# miniProIR.net
KiCad netlist of a schematic drawn in EAGLE
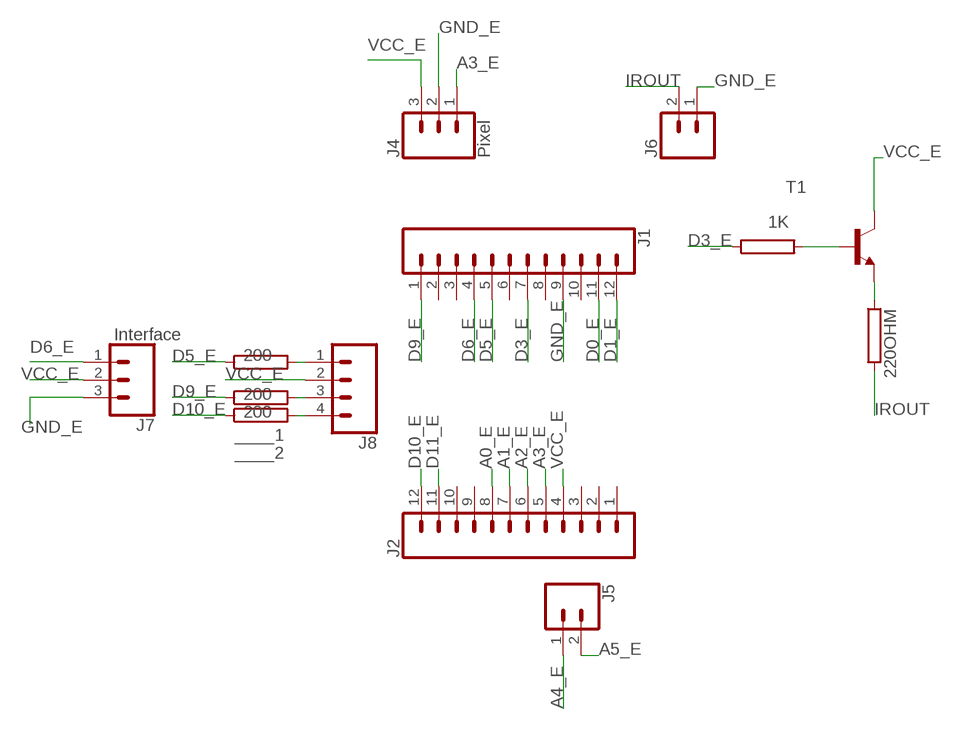
[diagram p0: schematic, sheet 1]

(export (version "E")
  (design (tool "Eeschema 10.0.6"))
  (components
    (comp (ref "1K")
      (value "RCA0001")
      (footprint "eagle-import:CA0001")
      (libsource (lib "eagle-import") (part "RCA0001"))
    )
    (comp (ref "200")
      (value "RCA0001")
      (footprint "eagle-import:CA0001")
      (libsource (lib "eagle-import") (part "RCA0001"))
    )
    (comp (ref "220OHM")
      (value "RCA0001")
      (footprint "eagle-import:CA0001")
      (libsource (lib "eagle-import") (part "RCA0001"))
    )
    (comp (ref "J1")
      (value "CONN_12")
      (footprint "eagle-import:1X12")
      (libsource (lib "eagle-import") (part "CONN_12"))
    )
    (comp (ref "J2")
      (value "CONN_12")
      (footprint "eagle-import:1X12")
      (libsource (lib "eagle-import") (part "CONN_12"))
    )
    (comp (ref "J4")
      (value "Pixel")
      (footprint "eagle-import:1X03")
      (libsource (lib "eagle-import") (part "CONN_03"))
    )
    (comp (ref "J5")
      (value "CONN_02")
      (footprint "eagle-import:1X02")
      (libsource (lib "eagle-import") (part "CONN_02"))
    )
    (comp (ref "J6")
      (value "CONN_02")
      (footprint "eagle-import:1X02")
      (libsource (lib "eagle-import") (part "CONN_02"))
    )
    (comp (ref "J7")
      (value "Interface")
      (footprint "eagle-import:1X03")
      (libsource (lib "eagle-import") (part "CONN_03"))
    )
    (comp (ref "J8")
      (value "CONN_04")
      (footprint "eagle-import:1X04")
      (libsource (lib "eagle-import") (part "CONN_04"))
    )
    (comp (ref "T1")
      (value "29-NPN-TO92-EBC")
      (footprint "eagle-import:TO92-EBC")
      (libsource (lib "eagle-import") (part "-NPN-TO92-EBC29"))
    )
    (comp (ref "____1")
      (value "200")
      (footprint "eagle-import:CA0001")
      (libsource (lib "eagle-import") (part "RCA0001"))
    )
    (comp (ref "____2")
      (value "200")
      (footprint "eagle-import:CA0001")
      (libsource (lib "eagle-import") (part "RCA0001"))
    )
  )
  (nets
    (net (code "1") (name "/A0_E") (class "Default")
      (node (ref "J2") (pin "8") (pinfunction "8_8") (pintype "passive"))
    )
    (net (code "2") (name "/A1_E") (class "Default")
      (node (ref "J2") (pin "7") (pinfunction "7_7") (pintype "passive"))
    )
    (net (code "3") (name "/A2_E") (class "Default")
      (node (ref "J2") (pin "6") (pinfunction "6_6") (pintype "passive"))
    )
    (net (code "4") (name "/A3_E") (class "Default")
      (node (ref "J2") (pin "5") (pinfunction "5_5") (pintype "passive"))
      (node (ref "J4") (pin "1") (pinfunction "1_1") (pintype "passive"))
    )
    (net (code "5") (name "/A4_E") (class "Default")
      (node (ref "J5") (pin "1") (pinfunction "1_1") (pintype "passive"))
    )
    (net (code "6") (name "/A5_E") (class "Default")
      (node (ref "J5") (pin "2") (pinfunction "2_2") (pintype "passive"))
    )
    (net (code "7") (name "/D0_E") (class "Default")
      (node (ref "J1") (pin "11") (pinfunction "11_11") (pintype "passive"))
    )
    (net (code "8") (name "/D1_E") (class "Default")
      (node (ref "J1") (pin "12") (pinfunction "12_12") (pintype "passive"))
    )
    (net (code "9") (name "/D3_E") (class "Default")
      (node (ref "1K") (pin "1") (pinfunction "1_1") (pintype "passive"))
      (node (ref "J1") (pin "7") (pinfunction "7_7") (pintype "passive"))
    )
    (net (code "10") (name "/D5_E") (class "Default")
      (node (ref "200") (pin "1") (pinfunction "1_1") (pintype "passive"))
      (node (ref "J1") (pin "5") (pinfunction "5_5") (pintype "passive"))
    )
    (net (code "11") (name "/D6_E") (class "Default")
      (node (ref "J1") (pin "4") (pinfunction "4_4") (pintype "passive"))
      (node (ref "J7") (pin "1") (pinfunction "1_1") (pintype "passive"))
    )
    (net (code "12") (name "/D9_E") (class "Default")
      (node (ref "J1") (pin "1") (pinfunction "1_1") (pintype "passive"))
      (node (ref "____1") (pin "1") (pinfunction "1_1") (pintype "passive"))
    )
    (net (code "13") (name "/D10_E") (class "Default")
      (node (ref "J2") (pin "12") (pinfunction "12_12") (pintype "passive"))
      (node (ref "____2") (pin "1") (pinfunction "1_1") (pintype "passive"))
    )
    (net (code "14") (name "/D11_E") (class "Default")
      (node (ref "J2") (pin "11") (pinfunction "11_11") (pintype "passive"))
    )
    (net (code "15") (name "/GND_E") (class "Default")
      (node (ref "J1") (pin "9") (pinfunction "9_9") (pintype "passive"))
      (node (ref "J4") (pin "2") (pinfunction "2_2") (pintype "passive"))
      (node (ref "J6") (pin "1") (pinfunction "1_1") (pintype "passive"))
      (node (ref "J7") (pin "3") (pinfunction "3_3") (pintype "passive"))
    )
    (net (code "16") (name "/IROUT") (class "Default")
      (node (ref "220OHM") (pin "2") (pinfunction "2_2") (pintype "passive"))
      (node (ref "J6") (pin "2") (pinfunction "2_2") (pintype "passive"))
    )
    (net (code "17") (name "/VCC_E") (class "Default")
      (node (ref "J2") (pin "4") (pinfunction "4_4") (pintype "passive"))
      (node (ref "J4") (pin "3") (pinfunction "3_3") (pintype "passive"))
      (node (ref "J7") (pin "2") (pinfunction "2_2") (pintype "passive"))
      (node (ref "J8") (pin "2") (pinfunction "2_2") (pintype "passive"))
      (node (ref "T1") (pin "C") (pinfunction "C_C") (pintype "passive"))
    )
    (net (code "18") (name "Net-(1K-Pad2)") (class "Default")
      (node (ref "1K") (pin "2") (pinfunction "2_2") (pintype "passive"))
      (node (ref "T1") (pin "B") (pinfunction "B_B") (pintype "passive"))
    )
    (net (code "19") (name "Net-(200-Pad2)") (class "Default")
      (node (ref "200") (pin "2") (pinfunction "2_2") (pintype "passive"))
      (node (ref "J8") (pin "1") (pinfunction "1_1") (pintype "passive"))
    )
    (net (code "20") (name "Net-(220OHM-Pad1)") (class "Default")
      (node (ref "220OHM") (pin "1") (pinfunction "1_1") (pintype "passive"))
      (node (ref "T1") (pin "E") (pinfunction "E_E") (pintype "passive"))
    )
    (net (code "21") (name "Net-(J8-Pad3)") (class "Default")
      (node (ref "J8") (pin "3") (pinfunction "3_3") (pintype "passive"))
      (node (ref "____1") (pin "2") (pinfunction "2_2") (pintype "passive"))
    )
    (net (code "22") (name "Net-(J8-Pad4)") (class "Default")
      (node (ref "J8") (pin "4") (pinfunction "4_4") (pintype "passive"))
      (node (ref "____2") (pin "2") (pinfunction "2_2") (pintype "passive"))
    )
    (net (code "23") (name "unconnected-(J1-Pad2)") (class "Default")
      (node (ref "J1") (pin "2") (pinfunction "2_2") (pintype "passive"))
    )
    (net (code "24") (name "unconnected-(J1-Pad3)") (class "Default")
      (node (ref "J1") (pin "3") (pinfunction "3_3") (pintype "passive"))
    )
    (net (code "25") (name "unconnected-(J1-Pad6)") (class "Default")
      (node (ref "J1") (pin "6") (pinfunction "6_6") (pintype "passive"))
    )
    (net (code "26") (name "unconnected-(J1-Pad8)") (class "Default")
      (node (ref "J1") (pin "8") (pinfunction "8_8") (pintype "passive"))
    )
    (net (code "27") (name "unconnected-(J1-Pad10)") (class "Default")
      (node (ref "J1") (pin "10") (pinfunction "10_10") (pintype "passive"))
    )
    (net (code "28") (name "unconnected-(J2-Pad1)") (class "Default")
      (node (ref "J2") (pin "1") (pinfunction "1_1") (pintype "passive"))
    )
    (net (code "29") (name "unconnected-(J2-Pad2)") (class "Default")
      (node (ref "J2") (pin "2") (pinfunction "2_2") (pintype "passive"))
    )
    (net (code "30") (name "unconnected-(J2-Pad3)") (class "Default")
      (node (ref "J2") (pin "3") (pinfunction "3_3") (pintype "passive"))
    )
    (net (code "31") (name "unconnected-(J2-Pad9)") (class "Default")
      (node (ref "J2") (pin "9") (pinfunction "9_9") (pintype "passive"))
    )
    (net (code "32") (name "unconnected-(J2-Pad10)") (class "Default")
      (node (ref "J2") (pin "10") (pinfunction "10_10") (pintype "passive"))
    )
  )
)
